# power_supply_smd.net
KiCad netlist of a schematic drawn in EAGLE
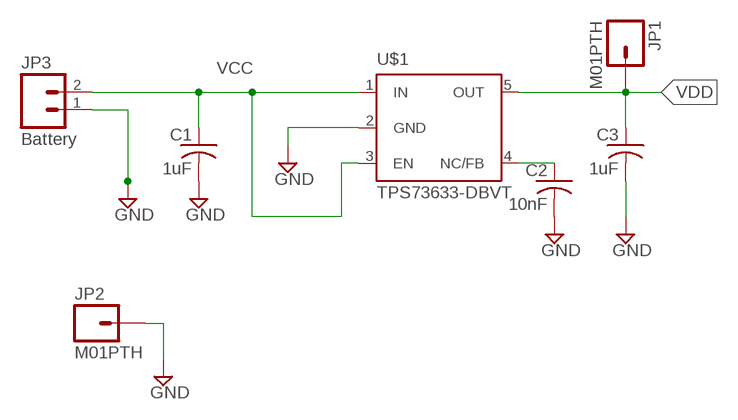
[diagram p0: schematic, sheet 1]

(export (version "E")
  (design (tool "Eeschema 10.0.6"))
  (components
    (comp (ref "C1")
      (value "1uF")
      (footprint "eagle-import:C0805")
      (libsource (lib "eagle-import") (part "C-USC0805"))
    )
    (comp (ref "C2")
      (value "10nF")
      (footprint "eagle-import:C0805")
      (libsource (lib "eagle-import") (part "C-USC0805"))
    )
    (comp (ref "C3")
      (value "1uF")
      (footprint "eagle-import:C0805")
      (libsource (lib "eagle-import") (part "C-USC0805"))
    )
    (comp (ref "JP1")
      (value "M01PTH")
      (footprint "eagle-import:1X01")
      (libsource (lib "eagle-import") (part "M01PTH"))
    )
    (comp (ref "JP2")
      (value "M01PTH")
      (footprint "eagle-import:1X01")
      (libsource (lib "eagle-import") (part "M01PTH"))
    )
    (comp (ref "JP3")
      (value "Battery")
      (footprint "eagle-import:1X02")
      (libsource (lib "eagle-import") (part "M02PTH"))
    )
    (comp (ref "U$1")
      (value "TPS73633-DBVT")
      (footprint "eagle-import:SOT23-DBV")
      (libsource (lib "eagle-import") (part "TPS73633-DBVT"))
    )
  )
  (nets
    (net (code "1") (name "/VCC") (class "Default")
      (node (ref "C1") (pin "1") (pinfunction "1_1") (pintype "passive"))
      (node (ref "JP3") (pin "2") (pinfunction "2_2") (pintype "passive"))
      (node (ref "U$1") (pin "1") (pinfunction "IN_1") (pintype "input"))
      (node (ref "U$1") (pin "3") (pinfunction "EN_3") (pintype "power_in"))
    )
    (net (code "2") (name "GND") (class "Default")
      (node (ref "C1") (pin "2") (pinfunction "2_2") (pintype "passive"))
      (node (ref "C2") (pin "2") (pinfunction "2_2") (pintype "passive"))
      (node (ref "C3") (pin "2") (pinfunction "2_2") (pintype "passive"))
      (node (ref "JP2") (pin "1") (pinfunction "1_1") (pintype "passive"))
      (node (ref "JP3") (pin "1") (pinfunction "1_1") (pintype "passive"))
      (node (ref "U$1") (pin "2") (pinfunction "GND_2") (pintype "input"))
    )
    (net (code "3") (name "Net-(U$1-NC{slash}FB)") (class "Default")
      (node (ref "C2") (pin "1") (pinfunction "1_1") (pintype "passive"))
      (node (ref "U$1") (pin "4") (pinfunction "NC/FB_4") (pintype "passive"))
    )
    (net (code "4") (name "VDD") (class "Default")
      (node (ref "C3") (pin "1") (pinfunction "1_1") (pintype "passive"))
      (node (ref "JP1") (pin "1") (pinfunction "1_1") (pintype "passive"))
      (node (ref "U$1") (pin "5") (pinfunction "OUT_5") (pintype "passive"))
    )
  )
)
